# AnalogSwitch.net
KiCad netlist of a schematic drawn in Altium Designer
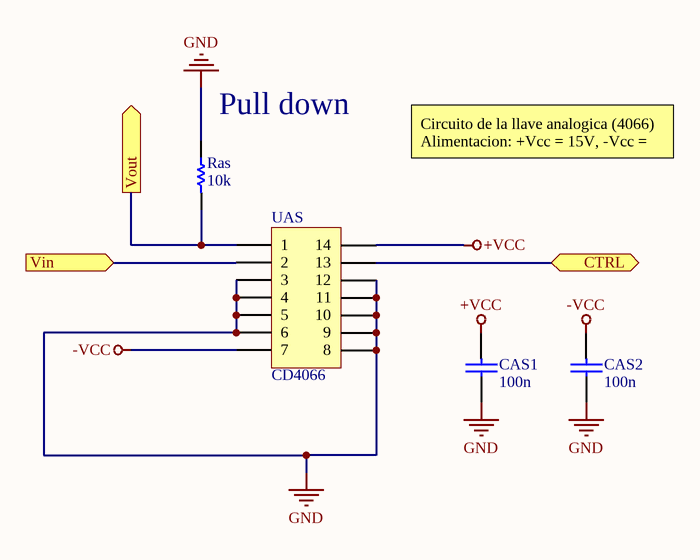
[diagram p0: AnalogSwitch.SchDoc]

(export (version "E")
  (design (tool "Eeschema 10.0.6"))
  (components
    (comp (ref "CAS1") (value "100n") (footprint "CAP200") (libsource (lib "Schematics") (part "CAP")))
    (comp (ref "CAS2") (value "100n") (footprint "CAP200") (libsource (lib "Schematics") (part "CAP")))
    (comp (ref "Ras") (value "10k") (footprint "RES400") (libsource (lib "Schematics") (part "RES")))
    (comp (ref "UAS") (value "CD4066") (footprint "DIP14") (libsource (lib "Schematics") (part "IC_DIP14")))
  )
  (nets
    (net (code "1") (name "+VCC") (class "Default")
      (node (ref "CAS1") (pin "1") (pinfunction "1_1") (pintype "passive"))
      (node (ref "UAS") (pin "14") (pinfunction "14_14") (pintype "passive"))
    )
    (net (code "2") (name "-VCC") (class "Default")
      (node (ref "CAS2") (pin "1") (pinfunction "1_1") (pintype "passive"))
      (node (ref "UAS") (pin "7") (pinfunction "7_7") (pintype "passive"))
    )
    (net (code "3") (name "/CTRL") (class "Default")
      (node (ref "UAS") (pin "13") (pinfunction "13_13") (pintype "passive"))
    )
    (net (code "4") (name "/Vin") (class "Default")
      (node (ref "UAS") (pin "2") (pinfunction "2_2") (pintype "passive"))
    )
    (net (code "5") (name "/Vout") (class "Default")
      (node (ref "Ras") (pin "2") (pinfunction "2_2") (pintype "passive"))
      (node (ref "UAS") (pin "1") (pinfunction "1_1") (pintype "passive"))
    )
    (net (code "6") (name "GND") (class "Default")
      (node (ref "CAS1") (pin "2") (pinfunction "2_2") (pintype "passive"))
      (node (ref "CAS2") (pin "2") (pinfunction "2_2") (pintype "passive"))
      (node (ref "Ras") (pin "1") (pinfunction "1_1") (pintype "passive"))
      (node (ref "UAS") (pin "10") (pinfunction "10_10") (pintype "passive"))
      (node (ref "UAS") (pin "11") (pinfunction "11_11") (pintype "passive"))
      (node (ref "UAS") (pin "12") (pinfunction "12_12") (pintype "passive"))
      (node (ref "UAS") (pin "3") (pinfunction "3_3") (pintype "passive"))
      (node (ref "UAS") (pin "4") (pinfunction "4_4") (pintype "passive"))
      (node (ref "UAS") (pin "5") (pinfunction "5_5") (pintype "passive"))
      (node (ref "UAS") (pin "6") (pinfunction "6_6") (pintype "passive"))
      (node (ref "UAS") (pin "8") (pinfunction "8_8") (pintype "passive"))
      (node (ref "UAS") (pin "9") (pinfunction "9_9") (pintype "passive"))
    )
  )
)
